# TinyFOC.net
KiCad netlist of a schematic drawn in EasyEDA Pro
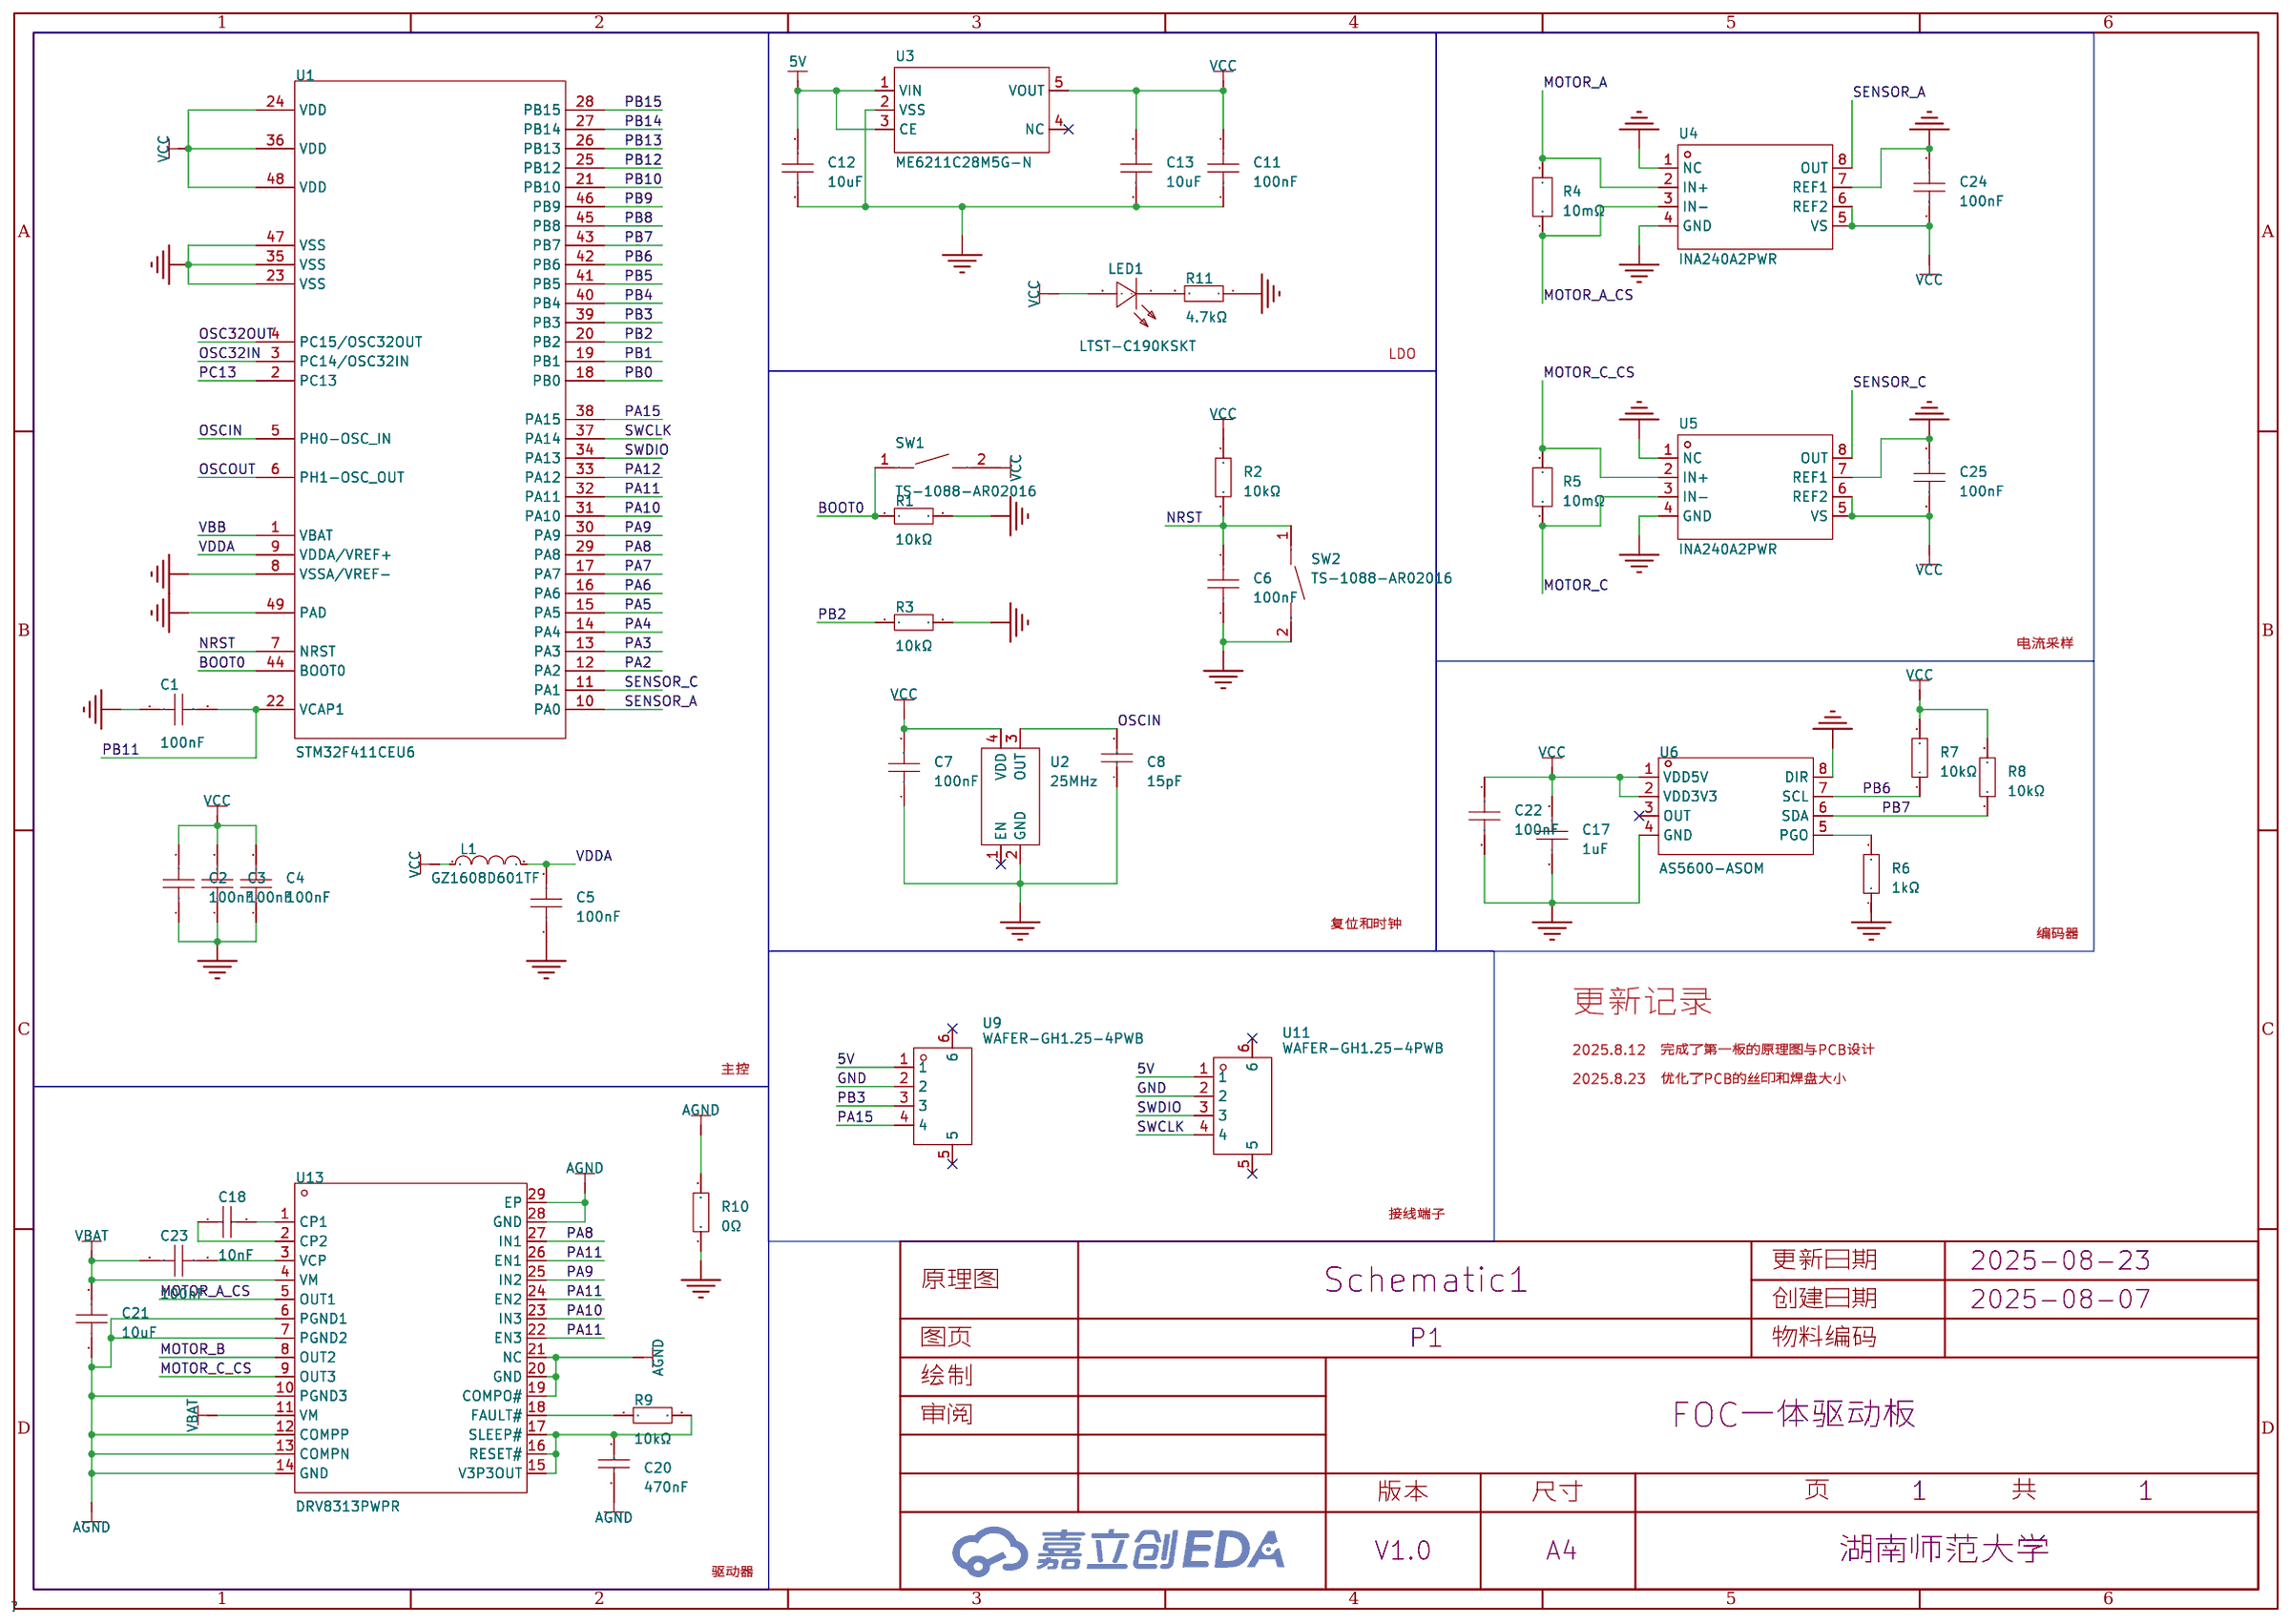
[diagram p0: schematic sheet]

(export (version "E")
  (design (tool "Eeschema 10.0.6"))
  (components
    (comp (ref "C1")
      (value "100nF")
      (footprint "easyedapro:C0603")
      (description "容值:100nF;精度:±10%;额定电压:50V;温度系数:X7R;")
      (fields
        (field (name "Manufacturer Part") "CGA0603X7R104K500JT")
        (field (name "Manufacturer") "HRE(芯声)")
      )
      (libsource (lib "easyedapro") (part "CGA0603X7R104K500JT"))
    )
    (comp (ref "C2")
      (value "100nF")
      (footprint "easyedapro:C0603")
      (description "容值:100nF;精度:±10%;额定电压:50V;温度系数:X7R;")
      (fields
        (field (name "Manufacturer Part") "CGA0603X7R104K500JT")
        (field (name "Manufacturer") "HRE(芯声)")
      )
      (libsource (lib "easyedapro") (part "CGA0603X7R104K500JT"))
    )
    (comp (ref "C3")
      (value "100nF")
      (footprint "easyedapro:C0603")
      (description "容值:100nF;精度:±10%;额定电压:50V;温度系数:X7R;")
      (fields
        (field (name "Manufacturer Part") "CGA0603X7R104K500JT")
        (field (name "Manufacturer") "HRE(芯声)")
      )
      (libsource (lib "easyedapro") (part "CGA0603X7R104K500JT"))
    )
    (comp (ref "C4")
      (value "100nF")
      (footprint "easyedapro:C0603")
      (description "容值:100nF;精度:±10%;额定电压:50V;温度系数:X7R;")
      (fields
        (field (name "Manufacturer Part") "CGA0603X7R104K500JT")
        (field (name "Manufacturer") "HRE(芯声)")
      )
      (libsource (lib "easyedapro") (part "CGA0603X7R104K500JT"))
    )
    (comp (ref "C5")
      (value "100nF")
      (footprint "easyedapro:C0603")
      (description "容值:100nF;精度:±10%;额定电压:50V;温度系数:X7R;")
      (fields
        (field (name "Manufacturer Part") "CGA0603X7R104K500JT")
        (field (name "Manufacturer") "HRE(芯声)")
      )
      (libsource (lib "easyedapro") (part "CGA0603X7R104K500JT"))
    )
    (comp (ref "C6")
      (value "100nF")
      (footprint "easyedapro:C0603")
      (description "容值:100nF;精度:±10%;额定电压:50V;温度系数:X7R;")
      (fields
        (field (name "Manufacturer Part") "CGA0603X7R104K500JT")
        (field (name "Manufacturer") "HRE(芯声)")
      )
      (libsource (lib "easyedapro") (part "CGA0603X7R104K500JT"))
    )
    (comp (ref "C7")
      (value "100nF")
      (footprint "easyedapro:C0603")
      (description "容值:100nF;精度:±10%;额定电压:50V;温度系数:X7R;")
      (fields
        (field (name "Manufacturer Part") "CGA0603X7R104K500JT")
        (field (name "Manufacturer") "HRE(芯声)")
      )
      (libsource (lib "easyedapro") (part "CGA0603X7R104K500JT"))
    )
    (comp (ref "C8")
      (value "15pF")
      (footprint "easyedapro:C0603")
      (description "容值:15pF;精度:±5%;额定电压:50V;材质(温度系数):C0G;")
      (fields
        (field (name "Manufacturer Part") "CL10C150JB8NNNC")
        (field (name "Manufacturer") "SAMSUNG(三星)")
      )
      (libsource (lib "easyedapro") (part "CL10C150JB8NNNC"))
    )
    (comp (ref "C11")
      (value "100nF")
      (footprint "easyedapro:C0603")
      (description "容值:100nF;精度:±10%;额定电压:50V;温度系数:X7R;")
      (fields
        (field (name "Manufacturer Part") "CGA0603X7R104K500JT")
        (field (name "Manufacturer") "HRE(芯声)")
      )
      (libsource (lib "easyedapro") (part "CGA0603X7R104K500JT"))
    )
    (comp (ref "C12")
      (value "10uF")
      (footprint "easyedapro:C0603")
      (description "容值:10uF;精度:±10%;额定电压:10V;材质(温度系数):X5R;")
      (fields
        (field (name "Manufacturer Part") "CL10A106KP8NNNC")
        (field (name "Manufacturer") "SAMSUNG(三星)")
      )
      (libsource (lib "easyedapro") (part "CL10A106KP8NNNC"))
    )
    (comp (ref "C13")
      (value "10uF")
      (footprint "easyedapro:C0603")
      (description "容值:10uF;精度:±10%;额定电压:10V;材质(温度系数):X5R;")
      (fields
        (field (name "Manufacturer Part") "CL10A106KP8NNNC")
        (field (name "Manufacturer") "SAMSUNG(三星)")
      )
      (libsource (lib "easyedapro") (part "CL10A106KP8NNNC"))
    )
    (comp (ref "C17")
      (value "1uF")
      (footprint "easyedapro:C0603")
      (description "容值:1uF;精度:±10%;额定电压:50V;材质(温度系数):X5R;")
      (fields
        (field (name "Manufacturer Part") "CL10A105KB8NNNC")
        (field (name "Manufacturer") "SAMSUNG(三星)")
      )
      (libsource (lib "easyedapro") (part "CL10A105KB8NNNC"))
    )
    (comp (ref "C18")
      (value "10nF")
      (footprint "easyedapro:C0805")
      (description "容值:10nF;精度:±10%;额定电压:50V;材质(温度系数):X7R;")
      (fields
        (field (name "Manufacturer Part") "CL21B103KBANNNC")
        (field (name "Manufacturer") "SAMSUNG(三星)")
      )
      (libsource (lib "easyedapro") (part "CL21B103KBANNNC"))
    )
    (comp (ref "C20")
      (value "470nF")
      (footprint "easyedapro:C0603")
      (description "容值:470nF;精度:±10%;额定电压:25V;材质(温度系数):X7R;")
      (fields
        (field (name "Manufacturer Part") "CL10B474KA8NNNC")
        (field (name "Manufacturer") "SAMSUNG(三星)")
      )
      (libsource (lib "easyedapro") (part "CL10B474KA8NNNC"))
    )
    (comp (ref "C21")
      (value "10uF")
      (footprint "easyedapro:C0603")
      (description "容值:10uF;精度:±20%;额定电压:25V;材质(温度系数):X5R;")
      (fields
        (field (name "Manufacturer Part") "CL10A106MA8NRNC")
        (field (name "Manufacturer") "SAMSUNG(三星)")
      )
      (libsource (lib "easyedapro") (part "CL10A106MA8NRNC"))
    )
    (comp (ref "C22")
      (value "100nF")
      (footprint "easyedapro:C0603")
      (description "容值:100nF;精度:±10%;额定电压:50V;温度系数:X7R;")
      (fields
        (field (name "Manufacturer Part") "CGA0603X7R104K500JT")
        (field (name "Manufacturer") "HRE(芯声)")
      )
      (libsource (lib "easyedapro") (part "CGA0603X7R104K500JT"))
    )
    (comp (ref "C23")
      (value "100nF")
      (footprint "easyedapro:C0603")
      (description "容值:100nF;精度:±10%;额定电压:50V;温度系数:X7R;")
      (fields
        (field (name "Manufacturer Part") "CGA0603X7R104K500JT")
        (field (name "Manufacturer") "HRE(芯声)")
      )
      (libsource (lib "easyedapro") (part "CGA0603X7R104K500JT"))
    )
    (comp (ref "C24")
      (value "100nF")
      (footprint "easyedapro:C0603")
      (description "容值:100nF;精度:±10%;额定电压:50V;温度系数:X7R;")
      (fields
        (field (name "Manufacturer Part") "CGA0603X7R104K500JT")
        (field (name "Manufacturer") "HRE(芯声)")
      )
      (libsource (lib "easyedapro") (part "CGA0603X7R104K500JT"))
    )
    (comp (ref "C25")
      (value "100nF")
      (footprint "easyedapro:C0603")
      (description "容值:100nF;精度:±10%;额定电压:50V;温度系数:X7R;")
      (fields
        (field (name "Manufacturer Part") "CGA0603X7R104K500JT")
        (field (name "Manufacturer") "HRE(芯声)")
      )
      (libsource (lib "easyedapro") (part "CGA0603X7R104K500JT"))
    )
    (comp (ref "L1")
      (value "GZ1608D601TF")
      (footprint "easyedapro:L0603")
      (description "阻抗 @ 频率:600Ω@100MHz;误差:±25%;直流电阻(DCR):450mΩ;")
      (fields (field (name "Manufacturer") "Sunlord(顺络)"))
      (libsource (lib "easyedapro") (part "GZ1608D601TF"))
    )
    (comp (ref "LED1")
      (value "LTST-C190KSKT")
      (footprint "easyedapro:LED0603-RD")
      (fields (field (name "Manufacturer") "LITEON(光宝)"))
      (libsource (lib "easyedapro") (part "LTST-C190KSKT"))
    )
    (comp (ref "R1")
      (value "10kΩ")
      (footprint "easyedapro:R0603")
      (description "电阻类型:厚膜电阻;阻值:10kΩ;精度:±1%;功率:100mW;工作电压:75V;温度系数:±100ppm/°C;")
      (fields
        (field (name "Manufacturer Part") "0603WAF1002T5E")
        (field (name "Manufacturer") "UNI-ROYAL(厚声)")
      )
      (libsource (lib "easyedapro") (part "0603WAF1002T5E"))
    )
    (comp (ref "R2")
      (value "10kΩ")
      (footprint "easyedapro:R0603")
      (description "电阻类型:厚膜电阻;阻值:10kΩ;精度:±1%;功率:100mW;工作电压:75V;温度系数:±100ppm/°C;")
      (fields
        (field (name "Manufacturer Part") "0603WAF1002T5E")
        (field (name "Manufacturer") "UNI-ROYAL(厚声)")
      )
      (libsource (lib "easyedapro") (part "0603WAF1002T5E"))
    )
    (comp (ref "R3")
      (value "10kΩ")
      (footprint "easyedapro:R0603")
      (description "电阻类型:厚膜电阻;阻值:10kΩ;精度:±1%;功率:100mW;工作电压:75V;温度系数:±100ppm/°C;")
      (fields
        (field (name "Manufacturer Part") "0603WAF1002T5E")
        (field (name "Manufacturer") "UNI-ROYAL(厚声)")
      )
      (libsource (lib "easyedapro") (part "0603WAF1002T5E"))
    )
    (comp (ref "R4")
      (value "10mΩ")
      (footprint "easyedapro:R1206")
      (description "电阻类型:采样电阻;阻值:10mΩ;精度:±1%;功率:1W;温度系数:±50ppm/°C;")
      (fields (field (name "Manufacturer Part") "JER1206F1R010") (field (name "Manufacturer") "捷而瑞"))
      (libsource (lib "easyedapro") (part "JER1206F1R010"))
    )
    (comp (ref "R5")
      (value "10mΩ")
      (footprint "easyedapro:R1206")
      (description "电阻类型:采样电阻;阻值:10mΩ;精度:±1%;功率:1W;温度系数:±50ppm/°C;")
      (fields (field (name "Manufacturer Part") "JER1206F1R010") (field (name "Manufacturer") "捷而瑞"))
      (libsource (lib "easyedapro") (part "JER1206F1R010"))
    )
    (comp (ref "R6")
      (value "1kΩ")
      (footprint "easyedapro:R0603")
      (description "电阻类型:厚膜电阻;阻值:1kΩ;精度:±1%;功率:100mW;最大工作电压:75V;温度系数:±100ppm/°C;")
      (fields
        (field (name "Manufacturer Part") "0603WAF1001T5E")
        (field (name "Manufacturer") "UNI-ROYAL(厚声)")
      )
      (libsource (lib "easyedapro") (part "0603WAF1001T5E"))
    )
    (comp (ref "R7")
      (value "10kΩ")
      (footprint "easyedapro:R0603")
      (description "电阻类型:厚膜电阻;阻值:10kΩ;精度:±1%;功率:100mW;工作电压:75V;温度系数:±100ppm/°C;")
      (fields
        (field (name "Manufacturer Part") "0603WAF1002T5E")
        (field (name "Manufacturer") "UNI-ROYAL(厚声)")
      )
      (libsource (lib "easyedapro") (part "0603WAF1002T5E"))
    )
    (comp (ref "R8")
      (value "10kΩ")
      (footprint "easyedapro:R0603")
      (description "电阻类型:厚膜电阻;阻值:10kΩ;精度:±1%;功率:100mW;工作电压:75V;温度系数:±100ppm/°C;")
      (fields
        (field (name "Manufacturer Part") "0603WAF1002T5E")
        (field (name "Manufacturer") "UNI-ROYAL(厚声)")
      )
      (libsource (lib "easyedapro") (part "0603WAF1002T5E"))
    )
    (comp (ref "R9")
      (value "10kΩ")
      (footprint "easyedapro:R0603")
      (description "电阻类型:厚膜电阻;阻值:10kΩ;精度:±1%;功率:100mW;工作电压:75V;温度系数:±100ppm/°C;")
      (fields
        (field (name "Manufacturer Part") "0603WAF1002T5E")
        (field (name "Manufacturer") "UNI-ROYAL(厚声)")
      )
      (libsource (lib "easyedapro") (part "0603WAF1002T5E"))
    )
    (comp (ref "R10")
      (value "0Ω")
      (footprint "easyedapro:R0603")
      (description "电阻类型:厚膜电阻;阻值:0Ω;精度:±1%;功率:100mW;工作电压:75V;")
      (fields
        (field (name "Manufacturer Part") "0603WAF0000T5E")
        (field (name "Manufacturer") "UNI-ROYAL(厚声)")
      )
      (libsource (lib "easyedapro") (part "0603WAF0000T5E"))
    )
    (comp (ref "R11")
      (value "4.7kΩ")
      (footprint "easyedapro:R0603")
      (description "电阻类型:厚膜电阻;阻值:4.7kΩ;精度:±1%;功率:100mW;最大工作电压:75V;温度系数:±100ppm/°C;")
      (fields
        (field (name "Manufacturer Part") "0603WAF4701T5E")
        (field (name "Manufacturer") "UNI-ROYAL(厚声)")
      )
      (libsource (lib "easyedapro") (part "0603WAF4701T5E"))
    )
    (comp (ref "SW1")
      (value "TS-1088-AR02016")
      (footprint "easyedapro:SW-SMD_L3.9-W3.0-P4.45")
      (fields (field (name "Manufacturer") "XUNPU(讯普)"))
      (libsource (lib "easyedapro") (part "TS-1088-AR02016"))
    )
    (comp (ref "SW2")
      (value "TS-1088-AR02016")
      (footprint "easyedapro:SW-SMD_L3.9-W3.0-P4.45")
      (fields (field (name "Manufacturer") "XUNPU(讯普)"))
      (libsource (lib "easyedapro") (part "TS-1088-AR02016"))
    )
    (comp (ref "U1")
      (value "STM32F411CEU6")
      (footprint "easyedapro:UFQFPN-48_L7.0-W7.0-P0.50-BL-EP")
      (description "CPU内核:ARM-M4;CPU最大主频:100MHz;应用领域:-;")
      (fields (field (name "Manufacturer") "ST(意法半导体)"))
      (libsource (lib "easyedapro") (part "STM32F411CEU6"))
    )
    (comp (ref "U2")
      (value "25MHz")
      (footprint "easyedapro:OSC-SMD_4P-L2.0-W1.6-BL")
      (description "频率:25MHz;")
      (fields (field (name "Manufacturer Part") "8T025000301") (field (name "Manufacturer") "HD(浩都频率)"))
      (libsource (lib "easyedapro") (part "8T025000301"))
    )
    (comp (ref "U3")
      (value "ME6211C28M5G-N")
      (footprint "easyedapro:SOT-23-5_L3.0-W1.7-P0.95-LS2.8-BR")
      (description "输出类型:固定;工作电压:6V;输出电压:2.8V;输出电流:450mA;电源纹波抑制比(PSRR):70dB@(1kHz);输出极性:正极;")
      (fields (field (name "Manufacturer") "MICRONE(南京微盟)"))
      (libsource (lib "easyedapro") (part "ME6211C28M5G"))
    )
    (comp (ref "U4")
      (value "INA240A2PWR")
      (footprint "easyedapro:TSSOP-8_L4.4-W3.0-P0.65-LS6.4-BL")
      (description "放大器数:单路;")
      (fields (field (name "Manufacturer") "TI(德州仪器)"))
      (libsource (lib "easyedapro") (part "INA240A2PWR"))
    )
    (comp (ref "U5")
      (value "INA240A2PWR")
      (footprint "easyedapro:TSSOP-8_L4.4-W3.0-P0.65-LS6.4-BL")
      (description "放大器数:单路;")
      (fields (field (name "Manufacturer") "TI(德州仪器)"))
      (libsource (lib "easyedapro") (part "INA240A2PWR"))
    )
    (comp (ref "U6")
      (value "AS5600-ASOM")
      (footprint "easyedapro:SOIC-8_L5.0-W4.0-P1.27-LS6.0-BL")
      (description "旋转角度范围:0°~360°;")
      (fields (field (name "Manufacturer") "ams(艾迈斯半导体)"))
      (libsource (lib "easyedapro") (part "AS5600-ASOM"))
    )
    (comp (ref "U9")
      (value "WAFER-GH1.25-4PWB")
      (footprint "easyedapro:CONN-SMD_4P-P1.25_XUNPU_WAFER-GH1.25-4PWB")
      (fields (field (name "Manufacturer") "XUNPU(讯普)"))
      (libsource (lib "easyedapro") (part "WAFER-GH1.25-4PWB"))
    )
    (comp (ref "U11")
      (value "WAFER-GH1.25-4PWB")
      (footprint "easyedapro:CONN-SMD_4P-P1.25_XUNPU_WAFER-GH1.25-4PWB")
      (fields (field (name "Manufacturer") "XUNPU(讯普)"))
      (libsource (lib "easyedapro") (part "WAFER-GH1.25-4PWB"))
    )
    (comp (ref "U13")
      (value "DRV8313PWPR")
      (footprint "easyedapro:HTSSOP-28_L9.8-W4.5-P0.65-LS6.6-BL-EP")
      (description "DRV8313 具有集成 FET、65V 最大电压、3A 峰值电流的三相电机驱动器")
      (fields (field (name "Manufacturer") "TI(德州仪器)"))
      (libsource (lib "easyedapro") (part "DRV8313PWPR"))
    )
  )
  (nets
    (net (code "1") (name "/BOOT0") (class "Default")
      (node (ref "R1") (pin "1") (pinfunction "1_1") (pintype "input"))
      (node (ref "SW1") (pin "1") (pinfunction "1_1") (pintype "unspecified"))
      (node (ref "U1") (pin "44") (pinfunction "BOOT0_44") (pintype "input"))
    )
    (net (code "2") (name "/MOTOR_A") (class "Default")
      (node (ref "R4") (pin "2") (pinfunction "2_2") (pintype "unspecified"))
      (node (ref "U4") (pin "2") (pinfunction "IN+_2") (pintype "unspecified"))
    )
    (net (code "3") (name "/MOTOR_A_CS") (class "Default")
      (node (ref "R4") (pin "1") (pinfunction "1_1") (pintype "unspecified"))
      (node (ref "U13") (pin "5") (pinfunction "OUT1_5") (pintype "unspecified"))
      (node (ref "U4") (pin "3") (pinfunction "IN-_3") (pintype "unspecified"))
    )
    (net (code "4") (name "/MOTOR_B") (class "Default")
      (node (ref "U13") (pin "8") (pinfunction "OUT2_8") (pintype "unspecified"))
    )
    (net (code "5") (name "/MOTOR_C") (class "Default")
      (node (ref "R5") (pin "1") (pinfunction "1_1") (pintype "unspecified"))
      (node (ref "U5") (pin "3") (pinfunction "IN-_3") (pintype "unspecified"))
    )
    (net (code "6") (name "/MOTOR_C_CS") (class "Default")
      (node (ref "R5") (pin "2") (pinfunction "2_2") (pintype "unspecified"))
      (node (ref "U13") (pin "9") (pinfunction "OUT3_9") (pintype "unspecified"))
      (node (ref "U5") (pin "2") (pinfunction "IN+_2") (pintype "unspecified"))
    )
    (net (code "7") (name "/NRST") (class "Default")
      (node (ref "C6") (pin "1") (pinfunction "1_1") (pintype "unspecified"))
      (node (ref "R2") (pin "2") (pinfunction "2_2") (pintype "input"))
      (node (ref "SW2") (pin "1") (pinfunction "1_1") (pintype "unspecified"))
      (node (ref "U1") (pin "7") (pinfunction "NRST_7") (pintype "unspecified"))
    )
    (net (code "8") (name "/OSC32IN") (class "Default")
      (node (ref "U1") (pin "3") (pinfunction "PC14/OSC32IN_3") (pintype "unspecified"))
    )
    (net (code "9") (name "/OSC32OUT") (class "Default")
      (node (ref "U1") (pin "4") (pinfunction "PC15/OSC32OUT_4") (pintype "unspecified"))
    )
    (net (code "10") (name "/OSCIN") (class "Default")
      (node (ref "C8") (pin "2") (pinfunction "2_2") (pintype "input"))
      (node (ref "U1") (pin "5") (pinfunction "PH0-OSC_IN_5") (pintype "unspecified"))
      (node (ref "U2") (pin "3") (pinfunction "OUT_3") (pintype "unspecified"))
    )
    (net (code "11") (name "/OSCOUT") (class "Default")
      (node (ref "U1") (pin "6") (pinfunction "PH1-OSC_OUT_6") (pintype "unspecified"))
    )
    (net (code "12") (name "/PA2") (class "Default")
      (node (ref "U1") (pin "12") (pinfunction "PA2_12") (pintype "unspecified"))
    )
    (net (code "13") (name "/PA3") (class "Default")
      (node (ref "U1") (pin "13") (pinfunction "PA3_13") (pintype "unspecified"))
    )
    (net (code "14") (name "/PA4") (class "Default")
      (node (ref "U1") (pin "14") (pinfunction "PA4_14") (pintype "unspecified"))
    )
    (net (code "15") (name "/PA5") (class "Default")
      (node (ref "U1") (pin "15") (pinfunction "PA5_15") (pintype "unspecified"))
    )
    (net (code "16") (name "/PA6") (class "Default")
      (node (ref "U1") (pin "16") (pinfunction "PA6_16") (pintype "unspecified"))
    )
    (net (code "17") (name "/PA7") (class "Default")
      (node (ref "U1") (pin "17") (pinfunction "PA7_17") (pintype "unspecified"))
    )
    (net (code "18") (name "/PA8") (class "Default")
      (node (ref "U1") (pin "29") (pinfunction "PA8_29") (pintype "unspecified"))
      (node (ref "U13") (pin "27") (pinfunction "IN1_27") (pintype "unspecified"))
    )
    (net (code "19") (name "/PA9") (class "Default")
      (node (ref "U1") (pin "30") (pinfunction "PA9_30") (pintype "unspecified"))
      (node (ref "U13") (pin "25") (pinfunction "IN2_25") (pintype "unspecified"))
    )
    (net (code "20") (name "/PA10") (class "Default")
      (node (ref "U1") (pin "31") (pinfunction "PA10_31") (pintype "unspecified"))
      (node (ref "U13") (pin "23") (pinfunction "IN3_23") (pintype "unspecified"))
    )
    (net (code "21") (name "/PA11") (class "Default")
      (node (ref "U1") (pin "32") (pinfunction "PA11_32") (pintype "unspecified"))
      (node (ref "U13") (pin "22") (pinfunction "EN3_22") (pintype "unspecified"))
      (node (ref "U13") (pin "24") (pinfunction "EN2_24") (pintype "unspecified"))
      (node (ref "U13") (pin "26") (pinfunction "EN1_26") (pintype "unspecified"))
    )
    (net (code "22") (name "/PA12") (class "Default")
      (node (ref "U1") (pin "33") (pinfunction "PA12_33") (pintype "unspecified"))
    )
    (net (code "23") (name "/PA15") (class "Default")
      (node (ref "U1") (pin "38") (pinfunction "PA15_38") (pintype "unspecified"))
      (node (ref "U9") (pin "4") (pinfunction "4_4") (pintype "unspecified"))
    )
    (net (code "24") (name "/PB0") (class "Default")
      (node (ref "U1") (pin "18") (pinfunction "PB0_18") (pintype "unspecified"))
    )
    (net (code "25") (name "/PB1") (class "Default")
      (node (ref "U1") (pin "19") (pinfunction "PB1_19") (pintype "unspecified"))
    )
    (net (code "26") (name "/PB2") (class "Default")
      (node (ref "R3") (pin "1") (pinfunction "1_1") (pintype "input"))
      (node (ref "U1") (pin "20") (pinfunction "PB2_20") (pintype "unspecified"))
    )
    (net (code "27") (name "/PB3") (class "Default")
      (node (ref "U1") (pin "39") (pinfunction "PB3_39") (pintype "unspecified"))
      (node (ref "U9") (pin "3") (pinfunction "3_3") (pintype "unspecified"))
    )
    (net (code "28") (name "/PB4") (class "Default")
      (node (ref "U1") (pin "40") (pinfunction "PB4_40") (pintype "unspecified"))
    )
    (net (code "29") (name "/PB5") (class "Default")
      (node (ref "U1") (pin "41") (pinfunction "PB5_41") (pintype "unspecified"))
    )
    (net (code "30") (name "/PB6") (class "Default")
      (node (ref "R7") (pin "1") (pinfunction "1_1") (pintype "input"))
      (node (ref "U1") (pin "42") (pinfunction "PB6_42") (pintype "unspecified"))
      (node (ref "U6") (pin "7") (pinfunction "SCL_7") (pintype "unspecified"))
    )
    (net (code "31") (name "/PB7") (class "Default")
      (node (ref "R8") (pin "1") (pinfunction "1_1") (pintype "input"))
      (node (ref "U1") (pin "43") (pinfunction "PB7_43") (pintype "unspecified"))
      (node (ref "U6") (pin "6") (pinfunction "SDA_6") (pintype "unspecified"))
    )
    (net (code "32") (name "/PB8") (class "Default")
      (node (ref "U1") (pin "45") (pinfunction "PB8_45") (pintype "unspecified"))
    )
    (net (code "33") (name "/PB9") (class "Default")
      (node (ref "U1") (pin "46") (pinfunction "PB9_46") (pintype "unspecified"))
    )
    (net (code "34") (name "/PB10") (class "Default")
      (node (ref "U1") (pin "21") (pinfunction "PB10_21") (pintype "unspecified"))
    )
    (net (code "35") (name "/PB11") (class "Default")
      (node (ref "C1") (pin "2") (pinfunction "2_2") (pintype "unspecified"))
      (node (ref "U1") (pin "22") (pinfunction "VCAP1_22") (pintype "unspecified"))
    )
    (net (code "36") (name "/PB12") (class "Default")
      (node (ref "U1") (pin "25") (pinfunction "PB12_25") (pintype "unspecified"))
    )
    (net (code "37") (name "/PB13") (class "Default")
      (node (ref "U1") (pin "26") (pinfunction "PB13_26") (pintype "unspecified"))
    )
    (net (code "38") (name "/PB14") (class "Default")
      (node (ref "U1") (pin "27") (pinfunction "PB14_27") (pintype "unspecified"))
    )
    (net (code "39") (name "/PB15") (class "Default")
      (node (ref "U1") (pin "28") (pinfunction "PB15_28") (pintype "unspecified"))
    )
    (net (code "40") (name "/PC13") (class "Default")
      (node (ref "U1") (pin "2") (pinfunction "PC13_2") (pintype "unspecified"))
    )
    (net (code "41") (name "/SENSOR_A") (class "Default")
      (node (ref "U1") (pin "10") (pinfunction "PA0_10") (pintype "unspecified"))
      (node (ref "U4") (pin "8") (pinfunction "OUT_8") (pintype "unspecified"))
    )
    (net (code "42") (name "/SENSOR_C") (class "Default")
      (node (ref "U1") (pin "11") (pinfunction "PA1_11") (pintype "unspecified"))
      (node (ref "U5") (pin "8") (pinfunction "OUT_8") (pintype "unspecified"))
    )
    (net (code "43") (name "/SWCLK") (class "Default")
      (node (ref "U1") (pin "37") (pinfunction "PA14_37") (pintype "unspecified"))
      (node (ref "U11") (pin "4") (pinfunction "4_4") (pintype "unspecified"))
    )
    (net (code "44") (name "/SWDIO") (class "Default")
      (node (ref "U1") (pin "34") (pinfunction "PA13_34") (pintype "unspecified"))
      (node (ref "U11") (pin "3") (pinfunction "3_3") (pintype "unspecified"))
    )
    (net (code "45") (name "/VBB") (class "Default")
      (node (ref "U1") (pin "1") (pinfunction "VBAT_1") (pintype "unspecified"))
    )
    (net (code "46") (name "/VDDA") (class "Default")
      (node (ref "C5") (pin "2") (pinfunction "2_2") (pintype "unspecified"))
      (node (ref "L1") (pin "2") (pinfunction "2_2") (pintype "unspecified"))
      (node (ref "U1") (pin "9") (pinfunction "VDDA/VREF+_9") (pintype "unspecified"))
    )
    (net (code "47") (name "5V") (class "Default")
      (node (ref "C12") (pin "2") (pinfunction "2_2") (pintype "unspecified"))
      (node (ref "U11") (pin "1") (pinfunction "1_1") (pintype "unspecified"))
      (node (ref "U3") (pin "1") (pinfunction "VIN_1") (pintype "unspecified"))
      (node (ref "U3") (pin "3") (pinfunction "CE_3") (pintype "unspecified"))
      (node (ref "U9") (pin "1") (pinfunction "1_1") (pintype "unspecified"))
    )
    (net (code "48") (name "AGND") (class "Default")
      (node (ref "C20") (pin "1") (pinfunction "1_1") (pintype "input"))
      (node (ref "C21") (pin "1") (pinfunction "1_1") (pintype "unspecified"))
      (node (ref "R10") (pin "2") (pinfunction "2_2") (pintype "input"))
      (node (ref "U13") (pin "10") (pinfunction "PGND3_10") (pintype "unspecified"))
      (node (ref "U13") (pin "12") (pinfunction "COMPP_12") (pintype "unspecified"))
      (node (ref "U13") (pin "13") (pinfunction "COMPN_13") (pintype "unspecified"))
      (node (ref "U13") (pin "14") (pinfunction "GND_14") (pintype "unspecified"))
      (node (ref "U13") (pin "19") (pinfunction "COMPO#_19") (pintype "unspecified"))
      (node (ref "U13") (pin "20") (pinfunction "GND_20") (pintype "unspecified"))
      (node (ref "U13") (pin "21") (pinfunction "NC_21") (pintype "unspecified"))
      (node (ref "U13") (pin "28") (pinfunction "GND_28") (pintype "unspecified"))
      (node (ref "U13") (pin "29") (pinfunction "EP_29") (pintype "unspecified"))
      (node (ref "U13") (pin "6") (pinfunction "PGND1_6") (pintype "unspecified"))
      (node (ref "U13") (pin "7") (pinfunction "PGND2_7") (pintype "unspecified"))
    )
    (net (code "49") (name "GND") (class "Default")
      (node (ref "C1") (pin "1") (pinfunction "1_1") (pintype "unspecified"))
      (node (ref "C11") (pin "1") (pinfunction "1_1") (pintype "unspecified"))
      (node (ref "C12") (pin "1") (pinfunction "1_1") (pintype "unspecified"))
      (node (ref "C13") (pin "1") (pinfunction "1_1") (pintype "unspecified"))
      (node (ref "C17") (pin "1") (pinfunction "1_1") (pintype "unspecified"))
      (node (ref "C2") (pin "1") (pinfunction "1_1") (pintype "unspecified"))
      (node (ref "C22") (pin "2") (pinfunction "2_2") (pintype "unspecified"))
      (node (ref "C24") (pin "2") (pinfunction "2_2") (pintype "unspecified"))
      (node (ref "C25") (pin "2") (pinfunction "2_2") (pintype "unspecified"))
      (node (ref "C3") (pin "1") (pinfunction "1_1") (pintype "unspecified"))
      (node (ref "C4") (pin "1") (pinfunction "1_1") (pintype "unspecified"))
      (node (ref "C5") (pin "1") (pinfunction "1_1") (pintype "unspecified"))
      (node (ref "C6") (pin "2") (pinfunction "2_2") (pintype "unspecified"))
      (node (ref "C7") (pin "1") (pinfunction "1_1") (pintype "unspecified"))
      (node (ref "C8") (pin "1") (pinfunction "1_1") (pintype "input"))
      (node (ref "R1") (pin "2") (pinfunction "2_2") (pintype "input"))
      (node (ref "R10") (pin "1") (pinfunction "1_1") (pintype "input"))
      (node (ref "R11") (pin "1") (pinfunction "1_1") (pintype "input"))
      (node (ref "R3") (pin "2") (pinfunction "2_2") (pintype "input"))
      (node (ref "R6") (pin "1") (pinfunction "1_1") (pintype "input"))
      (node (ref "SW2") (pin "2") (pinfunction "2_2") (pintype "unspecified"))
      (node (ref "U1") (pin "23") (pinfunction "VSS_23") (pintype "unspecified"))
      (node (ref "U1") (pin "35") (pinfunction "VSS_35") (pintype "unspecified"))
      (node (ref "U1") (pin "47") (pinfunction "VSS_47") (pintype "unspecified"))
      (node (ref "U1") (pin "49") (pinfunction "PAD_49") (pintype "unspecified"))
      (node (ref "U1") (pin "8") (pinfunction "VSSA/VREF-_8") (pintype "unspecified"))
      (node (ref "U11") (pin "2") (pinfunction "2_2") (pintype "unspecified"))
      (node (ref "U2") (pin "2") (pinfunction "GND_2") (pintype "unspecified"))
      (node (ref "U3") (pin "2") (pinfunction "VSS_2") (pintype "unspecified"))
      (node (ref "U4") (pin "1") (pinfunction "NC_1") (pintype "unspecified"))
      (node (ref "U4") (pin "4") (pinfunction "GND_4") (pintype "unspecified"))
      (node (ref "U4") (pin "7") (pinfunction "REF1_7") (pintype "unspecified"))
      (node (ref "U5") (pin "1") (pinfunction "NC_1") (pintype "unspecified"))
      (node (ref "U5") (pin "4") (pinfunction "GND_4") (pintype "unspecified"))
      (node (ref "U5") (pin "7") (pinfunction "REF1_7") (pintype "unspecified"))
      (node (ref "U6") (pin "4") (pinfunction "GND_4") (pintype "unspecified"))
      (node (ref "U6") (pin "8") (pinfunction "DIR_8") (pintype "unspecified"))
      (node (ref "U9") (pin "2") (pinfunction "2_2") (pintype "unspecified"))
    )
    (net (code "50") (name "Net-(LED1--)") (class "Default")
      (node (ref "LED1") (pin "1") (pinfunction "-_1") (pintype "unspecified"))
      (node (ref "R11") (pin "2") (pinfunction "2_2") (pintype "input"))
    )
    (net (code "51") (name "Net-(U6-PGO)") (class "Default")
      (node (ref "R6") (pin "2") (pinfunction "2_2") (pintype "input"))
      (node (ref "U6") (pin "5") (pinfunction "PGO_5") (pintype "unspecified"))
    )
    (net (code "52") (name "Net-(U13-CP1)") (class "Default")
      (node (ref "C18") (pin "2") (pinfunction "2_2") (pintype "input"))
      (node (ref "U13") (pin "1") (pinfunction "CP1_1") (pintype "unspecified"))
    )
    (net (code "53") (name "Net-(U13-CP2)") (class "Default")
      (node (ref "C18") (pin "1") (pinfunction "1_1") (pintype "input"))
      (node (ref "U13") (pin "2") (pinfunction "CP2_2") (pintype "unspecified"))
    )
    (net (code "54") (name "Net-(U13-FAULT#)") (class "Default")
      (node (ref "R9") (pin "1") (pinfunction "1_1") (pintype "input"))
      (node (ref "U13") (pin "18") (pinfunction "FAULT#_18") (pintype "unspecified"))
    )
    (net (code "55") (name "Net-(U13-RESET#)") (class "Default")
      (node (ref "C20") (pin "2") (pinfunction "2_2") (pintype "input"))
      (node (ref "R9") (pin "2") (pinfunction "2_2") (pintype "input"))
      (node (ref "U13") (pin "15") (pinfunction "V3P3OUT_15") (pintype "unspecified"))
      (node (ref "U13") (pin "16") (pinfunction "RESET#_16") (pintype "unspecified"))
      (node (ref "U13") (pin "17") (pinfunction "SLEEP#_17") (pintype "unspecified"))
    )
    (net (code "56") (name "Net-(U13-VCP)") (class "Default")
      (node (ref "C23") (pin "1") (pinfunction "1_1") (pintype "unspecified"))
      (node (ref "U13") (pin "3") (pinfunction "VCP_3") (pintype "unspecified"))
    )
    (net (code "57") (name "VBAT") (class "Default")
      (node (ref "C21") (pin "2") (pinfunction "2_2") (pintype "unspecified"))
      (node (ref "C23") (pin "2") (pinfunction "2_2") (pintype "unspecified"))
      (node (ref "U13") (pin "11") (pinfunction "VM_11") (pintype "unspecified"))
      (node (ref "U13") (pin "4") (pinfunction "VM_4") (pintype "unspecified"))
    )
    (net (code "58") (name "VCC") (class "Default")
      (node (ref "C11") (pin "2") (pinfunction "2_2") (pintype "unspecified"))
      (node (ref "C13") (pin "2") (pinfunction "2_2") (pintype "unspecified"))
      (node (ref "C17") (pin "2") (pinfunction "2_2") (pintype "unspecified"))
      (node (ref "C2") (pin "2") (pinfunction "2_2") (pintype "unspecified"))
      (node (ref "C22") (pin "1") (pinfunction "1_1") (pintype "unspecified"))
      (node (ref "C24") (pin "1") (pinfunction "1_1") (pintype "unspecified"))
      (node (ref "C25") (pin "1") (pinfunction "1_1") (pintype "unspecified"))
      (node (ref "C3") (pin "2") (pinfunction "2_2") (pintype "unspecified"))
      (node (ref "C4") (pin "2") (pinfunction "2_2") (pintype "unspecified"))
      (node (ref "C7") (pin "2") (pinfunction "2_2") (pintype "unspecified"))
      (node (ref "L1") (pin "1") (pinfunction "1_1") (pintype "unspecified"))
      (node (ref "LED1") (pin "2") (pinfunction "+_2") (pintype "unspecified"))
      (node (ref "R2") (pin "1") (pinfunction "1_1") (pintype "input"))
      (node (ref "R7") (pin "2") (pinfunction "2_2") (pintype "input"))
      (node (ref "R8") (pin "2") (pinfunction "2_2") (pintype "input"))
      (node (ref "SW1") (pin "2") (pinfunction "2_2") (pintype "unspecified"))
      (node (ref "U1") (pin "24") (pinfunction "VDD_24") (pintype "unspecified"))
      (node (ref "U1") (pin "36") (pinfunction "VDD_36") (pintype "unspecified"))
      (node (ref "U1") (pin "48") (pinfunction "VDD_48") (pintype "unspecified"))
      (node (ref "U2") (pin "4") (pinfunction "VDD_4") (pintype "unspecified"))
      (node (ref "U3") (pin "5") (pinfunction "VOUT_5") (pintype "unspecified"))
      (node (ref "U4") (pin "5") (pinfunction "VS_5") (pintype "unspecified"))
      (node (ref "U4") (pin "6") (pinfunction "REF2_6") (pintype "unspecified"))
      (node (ref "U5") (pin "5") (pinfunction "VS_5") (pintype "unspecified"))
      (node (ref "U5") (pin "6") (pinfunction "REF2_6") (pintype "unspecified"))
      (node (ref "U6") (pin "1") (pinfunction "VDD5V_1") (pintype "unspecified"))
      (node (ref "U6") (pin "2") (pinfunction "VDD3V3_2") (pintype "unspecified"))
    )
    (net (code "59") (name "unconnected-(U2-EN-Pad1)") (class "Default")
      (node (ref "U2") (pin "1") (pinfunction "EN_1") (pintype "unspecified+no_connect"))
    )
    (net (code "60") (name "unconnected-(U3-NC-Pad4)") (class "Default")
      (node (ref "U3") (pin "4") (pinfunction "NC_4") (pintype "unspecified+no_connect"))
    )
    (net (code "61") (name "unconnected-(U6-OUT-Pad3)") (class "Default")
      (node (ref "U6") (pin "3") (pinfunction "OUT_3") (pintype "unspecified+no_connect"))
    )
    (net (code "62") (name "unconnected-(U9-Pad5)") (class "Default")
      (node (ref "U9") (pin "5") (pinfunction "5_5") (pintype "unspecified+no_connect"))
    )
    (net (code "63") (name "unconnected-(U9-Pad6)") (class "Default")
      (node (ref "U9") (pin "6") (pinfunction "6_6") (pintype "unspecified+no_connect"))
    )
    (net (code "64") (name "unconnected-(U11-Pad5)") (class "Default")
      (node (ref "U11") (pin "5") (pinfunction "5_5") (pintype "unspecified+no_connect"))
    )
    (net (code "65") (name "unconnected-(U11-Pad6)") (class "Default")
      (node (ref "U11") (pin "6") (pinfunction "6_6") (pintype "unspecified+no_connect"))
    )
  )
)
